# 7SegClock.net
KiCad netlist of a schematic drawn in EAGLE
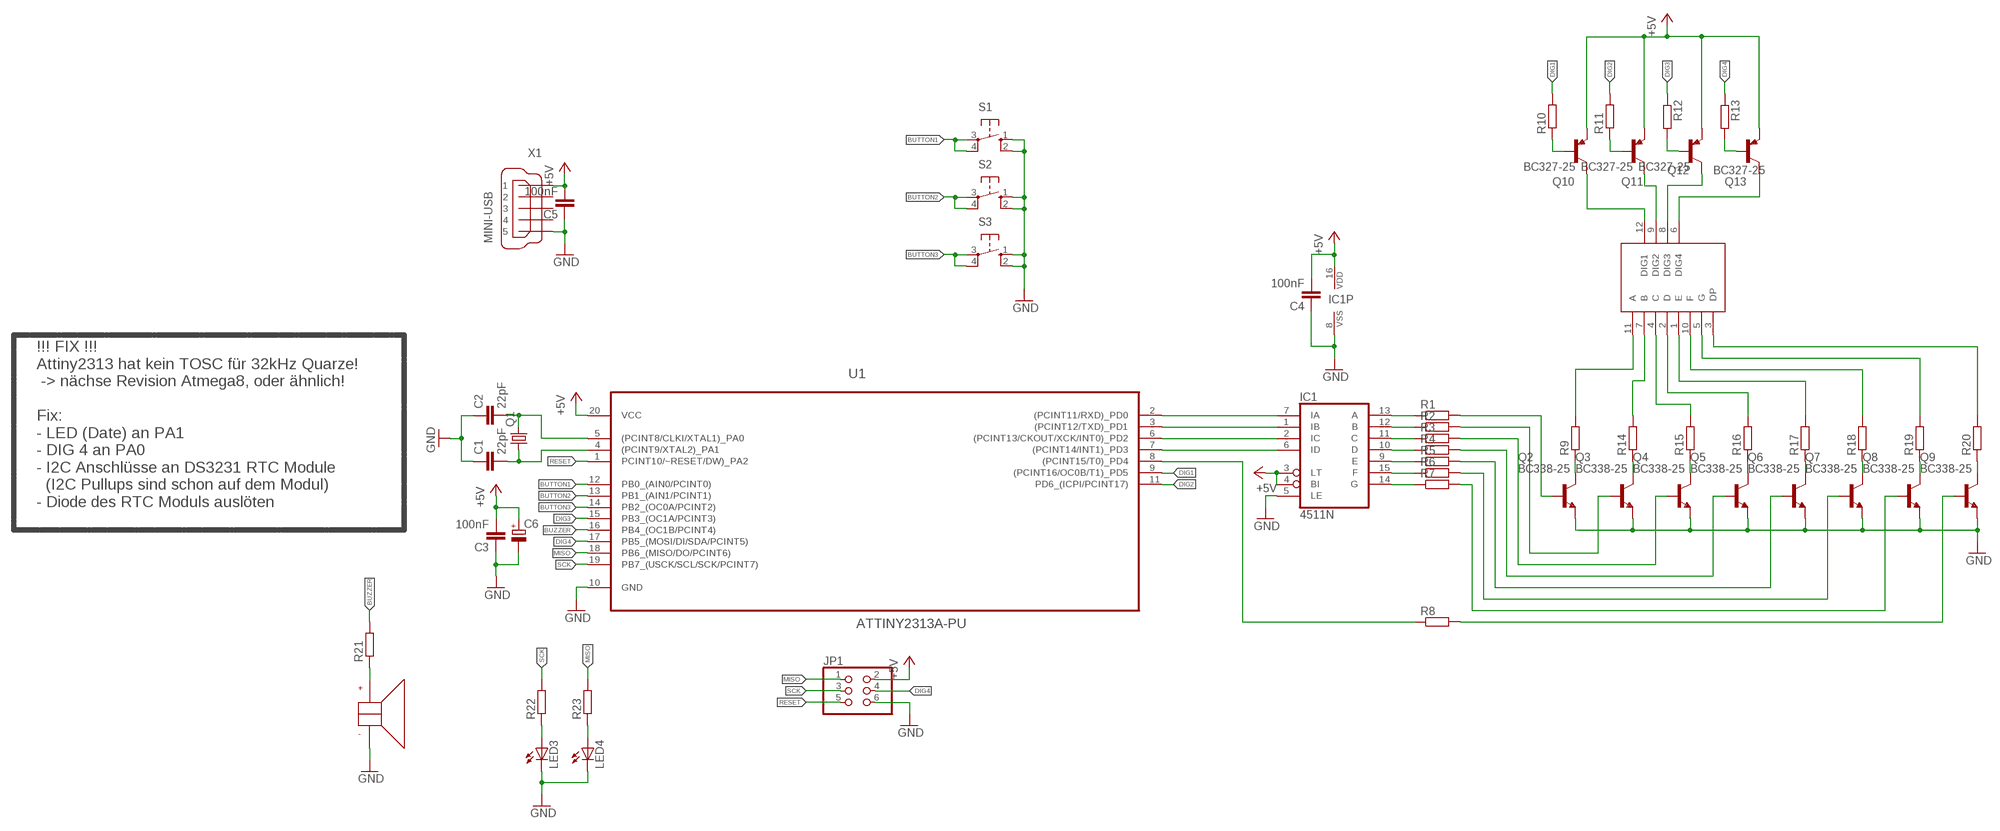
[diagram p0: schematic, sheet 1]

(export (version "E")
  (design (tool "Eeschema 10.0.6"))
  (components
    (comp (ref "C1")
      (value "22pF")
      (footprint "eagle-import:C025-025X050")
      (libsource (lib "eagle-import") (part "C-EU025-025X050"))
    )
    (comp (ref "C2")
      (value "22pF")
      (footprint "eagle-import:C025-025X050")
      (libsource (lib "eagle-import") (part "C-EU025-025X050"))
    )
    (comp (ref "C3")
      (value "100nF")
      (footprint "eagle-import:C025-025X050")
      (libsource (lib "eagle-import") (part "C-EU025-025X050"))
    )
    (comp (ref "C4")
      (value "100nF")
      (footprint "eagle-import:C025-025X050")
      (libsource (lib "eagle-import") (part "C-EU025-025X050"))
    )
    (comp (ref "C5")
      (value "100nF")
      (footprint "eagle-import:C025-025X050")
      (libsource (lib "eagle-import") (part "C-EU025-025X050"))
    )
    (comp (ref "C6")
      (value "CPOL-EUE2-5")
      (footprint "eagle-import:E2-5")
      (libsource (lib "eagle-import") (part "CPOL-EUE2-5"))
    )
    (comp (ref "IC1")
      (value "4511N")
      (footprint "eagle-import:DIL16")
      (libsource (lib "eagle-import") (part "4511N"))
    )
    (comp (ref "JP1")
      (value "PINHD-2X3")
      (footprint "eagle-import:2X03")
      (libsource (lib "eagle-import") (part "PINHD-2X3"))
    )
    (comp (ref "LED1")
      (value "7SEGCOMAN")
      (footprint "eagle-import:7SEGCOMAN")
      (libsource (lib "eagle-import") (part "7SEGCOMAN"))
    )
    (comp (ref "LED3")
      (value "LED3MM")
      (footprint "eagle-import:LED3MM")
      (libsource (lib "eagle-import") (part "LED3MM"))
    )
    (comp (ref "LED4")
      (value "LED3MM")
      (footprint "eagle-import:LED3MM")
      (libsource (lib "eagle-import") (part "LED3MM"))
    )
    (comp (ref "Q1")
      (value "CRYSTALTC38H")
      (footprint "eagle-import:TC38H")
      (libsource (lib "eagle-import") (part "CRYSTALTC38H"))
    )
    (comp (ref "Q2")
      (value "BC338-25")
      (footprint "eagle-import:TO92-EBC")
      (libsource (lib "eagle-import") (part "BC338-25"))
    )
    (comp (ref "Q3")
      (value "BC338-25")
      (footprint "eagle-import:TO92-EBC")
      (libsource (lib "eagle-import") (part "BC338-25"))
    )
    (comp (ref "Q4")
      (value "BC338-25")
      (footprint "eagle-import:TO92-EBC")
      (libsource (lib "eagle-import") (part "BC338-25"))
    )
    (comp (ref "Q5")
      (value "BC338-25")
      (footprint "eagle-import:TO92-EBC")
      (libsource (lib "eagle-import") (part "BC338-25"))
    )
    (comp (ref "Q6")
      (value "BC338-25")
      (footprint "eagle-import:TO92-EBC")
      (libsource (lib "eagle-import") (part "BC338-25"))
    )
    (comp (ref "Q7")
      (value "BC338-25")
      (footprint "eagle-import:TO92-EBC")
      (libsource (lib "eagle-import") (part "BC338-25"))
    )
    (comp (ref "Q8")
      (value "BC338-25")
      (footprint "eagle-import:TO92-EBC")
      (libsource (lib "eagle-import") (part "BC338-25"))
    )
    (comp (ref "Q9")
      (value "BC338-25")
      (footprint "eagle-import:TO92-EBC")
      (libsource (lib "eagle-import") (part "BC338-25"))
    )
    (comp (ref "Q10")
      (value "BC327-25")
      (footprint "eagle-import:TO92-EBC")
      (libsource (lib "eagle-import") (part "BC327-25"))
    )
    (comp (ref "Q11")
      (value "BC327-25")
      (footprint "eagle-import:TO92-EBC")
      (libsource (lib "eagle-import") (part "BC327-25"))
    )
    (comp (ref "Q12")
      (value "BC327-25")
      (footprint "eagle-import:TO92-EBC")
      (libsource (lib "eagle-import") (part "BC327-25"))
    )
    (comp (ref "Q13")
      (value "BC327-25")
      (footprint "eagle-import:TO92-EBC")
      (libsource (lib "eagle-import") (part "BC327-25"))
    )
    (comp (ref "R1")
      (value "R-EU_0207/7")
      (footprint "eagle-import:0207_7")
      (libsource (lib "eagle-import") (part "R-EU_0207/7"))
    )
    (comp (ref "R2")
      (value "R-EU_0207/7")
      (footprint "eagle-import:0207_7")
      (libsource (lib "eagle-import") (part "R-EU_0207/7"))
    )
    (comp (ref "R3")
      (value "R-EU_0207/7")
      (footprint "eagle-import:0207_7")
      (libsource (lib "eagle-import") (part "R-EU_0207/7"))
    )
    (comp (ref "R4")
      (value "R-EU_0207/7")
      (footprint "eagle-import:0207_7")
      (libsource (lib "eagle-import") (part "R-EU_0207/7"))
    )
    (comp (ref "R5")
      (value "R-EU_0207/7")
      (footprint "eagle-import:0207_7")
      (libsource (lib "eagle-import") (part "R-EU_0207/7"))
    )
    (comp (ref "R6")
      (value "R-EU_0207/7")
      (footprint "eagle-import:0207_7")
      (libsource (lib "eagle-import") (part "R-EU_0207/7"))
    )
    (comp (ref "R7")
      (value "R-EU_0207/7")
      (footprint "eagle-import:0207_7")
      (libsource (lib "eagle-import") (part "R-EU_0207/7"))
    )
    (comp (ref "R8")
      (value "R-EU_0207/7")
      (footprint "eagle-import:0207_7")
      (libsource (lib "eagle-import") (part "R-EU_0207/7"))
    )
    (comp (ref "R9")
      (value "R-EU_0207/7")
      (footprint "eagle-import:0207_7")
      (libsource (lib "eagle-import") (part "R-EU_0207/7"))
    )
    (comp (ref "R10")
      (value "R-EU_0207/7")
      (footprint "eagle-import:0207_7")
      (libsource (lib "eagle-import") (part "R-EU_0207/7"))
    )
    (comp (ref "R11")
      (value "R-EU_0207/7")
      (footprint "eagle-import:0207_7")
      (libsource (lib "eagle-import") (part "R-EU_0207/7"))
    )
    (comp (ref "R12")
      (value "R-EU_0207/7")
      (footprint "eagle-import:0207_7")
      (libsource (lib "eagle-import") (part "R-EU_0207/7"))
    )
    (comp (ref "R13")
      (value "R-EU_0207/7")
      (footprint "eagle-import:0207_7")
      (libsource (lib "eagle-import") (part "R-EU_0207/7"))
    )
    (comp (ref "R14")
      (value "R-EU_0207/7")
      (footprint "eagle-import:0207_7")
      (libsource (lib "eagle-import") (part "R-EU_0207/7"))
    )
    (comp (ref "R15")
      (value "R-EU_0207/7")
      (footprint "eagle-import:0207_7")
      (libsource (lib "eagle-import") (part "R-EU_0207/7"))
    )
    (comp (ref "R16")
      (value "R-EU_0207/7")
      (footprint "eagle-import:0207_7")
      (libsource (lib "eagle-import") (part "R-EU_0207/7"))
    )
    (comp (ref "R17")
      (value "R-EU_0207/7")
      (footprint "eagle-import:0207_7")
      (libsource (lib "eagle-import") (part "R-EU_0207/7"))
    )
    (comp (ref "R18")
      (value "R-EU_0207/7")
      (footprint "eagle-import:0207_7")
      (libsource (lib "eagle-import") (part "R-EU_0207/7"))
    )
    (comp (ref "R19")
      (value "R-EU_0207/7")
      (footprint "eagle-import:0207_7")
      (libsource (lib "eagle-import") (part "R-EU_0207/7"))
    )
    (comp (ref "R20")
      (value "R-EU_0207/7")
      (footprint "eagle-import:0207_7")
      (libsource (lib "eagle-import") (part "R-EU_0207/7"))
    )
    (comp (ref "R21")
      (value "R-EU_0207/7")
      (footprint "eagle-import:0207_7")
      (libsource (lib "eagle-import") (part "R-EU_0207/7"))
    )
    (comp (ref "R22")
      (value "R-EU_0207/7")
      (footprint "eagle-import:0207_7")
      (libsource (lib "eagle-import") (part "R-EU_0207/7"))
    )
    (comp (ref "R23")
      (value "R-EU_0207/7")
      (footprint "eagle-import:0207_7")
      (libsource (lib "eagle-import") (part "R-EU_0207/7"))
    )
    (comp (ref "S1")
      (value "10-XX")
      (footprint "eagle-import:B3F-10XX")
      (fields (field (name "MPN") "B3F-1000"))
      (libsource (lib "eagle-import") (part "10-XX"))
    )
    (comp (ref "S2")
      (value "10-XX")
      (footprint "eagle-import:B3F-10XX")
      (fields (field (name "MPN") "B3F-1000"))
      (libsource (lib "eagle-import") (part "10-XX"))
    )
    (comp (ref "S3")
      (value "10-XX")
      (footprint "eagle-import:B3F-10XX")
      (fields (field (name "MPN") "B3F-1000"))
      (libsource (lib "eagle-import") (part "10-XX"))
    )
    (comp (ref "U$1")
      (value "PIEZO_BUZZER_RM7,6")
      (footprint "eagle-import:PIEZO_BUZZER_RM7,6")
      (libsource (lib "eagle-import") (part "PIEZO_BUZZER_RM7,6"))
    )
    (comp (ref "U1")
      (value "ATTINY2313A-PU")
      (footprint "eagle-import:DIP254P762X533-20")
      (libsource (lib "eagle-import") (part "ATTINY2313A-PU"))
    )
    (comp (ref "X1")
      (value "MINI-USB")
      (footprint "eagle-import:32005-201")
      (libsource (lib "eagle-import") (part "MINI-USB-32005-201"))
    )
  )
  (nets
    (net (code "1") (name "+5V") (class "Default")
      (node (ref "C3") (pin "2") (pinfunction "2_2") (pintype "passive"))
      (node (ref "C4") (pin "2") (pinfunction "2_2") (pintype "passive"))
      (node (ref "C5") (pin "2") (pinfunction "2_2") (pintype "passive"))
      (node (ref "C6") (pin "+") (pinfunction "+_+") (pintype "passive"))
      (node (ref "IC1") (pin "16") (pinfunction "VDD_16") (pintype "power_in"))
      (node (ref "IC1") (pin "3") (pinfunction "LT_3") (pintype "input"))
      (node (ref "IC1") (pin "4") (pinfunction "BI_4") (pintype "input"))
      (node (ref "JP1") (pin "2") (pinfunction "2_2") (pintype "passive"))
      (node (ref "Q10") (pin "E") (pinfunction "E_E") (pintype "passive"))
      (node (ref "Q11") (pin "E") (pinfunction "E_E") (pintype "passive"))
      (node (ref "Q12") (pin "E") (pinfunction "E_E") (pintype "passive"))
      (node (ref "Q13") (pin "E") (pinfunction "E_E") (pintype "passive"))
      (node (ref "U1") (pin "20") (pinfunction "VCC_20") (pintype "power_in"))
      (node (ref "X1") (pin "1") (pinfunction "1_1") (pintype "passive"))
    )
    (net (code "2") (name "BUTTON1") (class "Default")
      (node (ref "S1") (pin "3") (pinfunction "P_3") (pintype "passive"))
      (node (ref "S1") (pin "4") (pinfunction "P1_4") (pintype "passive"))
      (node (ref "U1") (pin "12") (pinfunction "PB0_(AIN0/PCINT0)_12") (pintype "bidirectional"))
    )
    (net (code "3") (name "BUTTON2") (class "Default")
      (node (ref "S2") (pin "3") (pinfunction "P_3") (pintype "passive"))
      (node (ref "S2") (pin "4") (pinfunction "P1_4") (pintype "passive"))
      (node (ref "U1") (pin "13") (pinfunction "PB1_(AIN1/PCINT1)_13") (pintype "bidirectional"))
    )
    (net (code "4") (name "BUTTON3") (class "Default")
      (node (ref "S3") (pin "3") (pinfunction "P_3") (pintype "passive"))
      (node (ref "S3") (pin "4") (pinfunction "P1_4") (pintype "passive"))
      (node (ref "U1") (pin "14") (pinfunction "PB2_(OC0A/PCINT2)_14") (pintype "bidirectional"))
    )
    (net (code "5") (name "BUZZER") (class "Default")
      (node (ref "R21") (pin "2") (pinfunction "2_2") (pintype "passive"))
      (node (ref "U1") (pin "16") (pinfunction "PB4_(OC1B/PCINT4)_16") (pintype "bidirectional"))
    )
    (net (code "6") (name "DIG1") (class "Default")
      (node (ref "R10") (pin "2") (pinfunction "2_2") (pintype "passive"))
      (node (ref "U1") (pin "9") (pinfunction "(PCINT16/OC0B/T1)_PD5_9") (pintype "bidirectional"))
    )
    (net (code "7") (name "DIG2") (class "Default")
      (node (ref "R11") (pin "2") (pinfunction "2_2") (pintype "passive"))
      (node (ref "U1") (pin "11") (pinfunction "PD6_(ICPI/PCINT17)_11") (pintype "bidirectional"))
    )
    (net (code "8") (name "DIG3") (class "Default")
      (node (ref "R12") (pin "1") (pinfunction "1_1") (pintype "passive"))
      (node (ref "U1") (pin "15") (pinfunction "PB3_(OC1A/PCINT3)_15") (pintype "bidirectional"))
    )
    (net (code "9") (name "DIG4") (class "Default")
      (node (ref "JP1") (pin "4") (pinfunction "4_4") (pintype "passive"))
      (node (ref "R13") (pin "1") (pinfunction "1_1") (pintype "passive"))
      (node (ref "U1") (pin "17") (pinfunction "PB5_(MOSI/DI/SDA/PCINT5)_17") (pintype "bidirectional"))
    )
    (net (code "10") (name "GND") (class "Default")
      (node (ref "C1") (pin "1") (pinfunction "1_1") (pintype "passive"))
      (node (ref "C2") (pin "1") (pinfunction "1_1") (pintype "passive"))
      (node (ref "C3") (pin "1") (pinfunction "1_1") (pintype "passive"))
      (node (ref "C4") (pin "1") (pinfunction "1_1") (pintype "passive"))
      (node (ref "C5") (pin "1") (pinfunction "1_1") (pintype "passive"))
      (node (ref "C6") (pin "-") (pinfunction "-_-") (pintype "passive"))
      (node (ref "IC1") (pin "5") (pinfunction "LE_5") (pintype "input"))
      (node (ref "IC1") (pin "8") (pinfunction "VSS_8") (pintype "power_in"))
      (node (ref "JP1") (pin "6") (pinfunction "6_6") (pintype "passive"))
      (node (ref "LED3") (pin "K") (pinfunction "C_K") (pintype "passive"))
      (node (ref "LED4") (pin "K") (pinfunction "C_K") (pintype "passive"))
      (node (ref "Q2") (pin "E") (pinfunction "E_E") (pintype "passive"))
      (node (ref "Q3") (pin "E") (pinfunction "E_E") (pintype "passive"))
      (node (ref "Q4") (pin "E") (pinfunction "E_E") (pintype "passive"))
      (node (ref "Q5") (pin "E") (pinfunction "E_E") (pintype "passive"))
      (node (ref "Q6") (pin "E") (pinfunction "E_E") (pintype "passive"))
      (node (ref "Q7") (pin "E") (pinfunction "E_E") (pintype "passive"))
      (node (ref "Q8") (pin "E") (pinfunction "E_E") (pintype "passive"))
      (node (ref "Q9") (pin "E") (pinfunction "E_E") (pintype "passive"))
      (node (ref "S1") (pin "1") (pinfunction "S_1") (pintype "passive"))
      (node (ref "S1") (pin "2") (pinfunction "S1_2") (pintype "passive"))
      (node (ref "S2") (pin "1") (pinfunction "S_1") (pintype "passive"))
      (node (ref "S2") (pin "2") (pinfunction "S1_2") (pintype "passive"))
      (node (ref "S3") (pin "1") (pinfunction "S_1") (pintype "passive"))
      (node (ref "S3") (pin "2") (pinfunction "S1_2") (pintype "passive"))
      (node (ref "U$1") (pin "P$2") (pinfunction "P$2_P$2") (pintype "bidirectional"))
      (node (ref "U1") (pin "10") (pinfunction "GND_10") (pintype "passive"))
      (node (ref "X1") (pin "5") (pinfunction "5_5") (pintype "passive"))
    )
    (net (code "11") (name "MISO") (class "Default")
      (node (ref "JP1") (pin "1") (pinfunction "1_1") (pintype "passive"))
      (node (ref "R23") (pin "2") (pinfunction "2_2") (pintype "passive"))
      (node (ref "U1") (pin "18") (pinfunction "PB6_(MISO/DO/PCINT6)_18") (pintype "bidirectional"))
    )
    (net (code "12") (name "Net-(IC1A-A)") (class "Default")
      (node (ref "IC1") (pin "13") (pinfunction "A_13") (pintype "output"))
      (node (ref "R1") (pin "1") (pinfunction "1_1") (pintype "passive"))
    )
    (net (code "13") (name "Net-(IC1A-B)") (class "Default")
      (node (ref "IC1") (pin "12") (pinfunction "B_12") (pintype "output"))
      (node (ref "R2") (pin "1") (pinfunction "1_1") (pintype "passive"))
    )
    (net (code "14") (name "Net-(IC1A-C)") (class "Default")
      (node (ref "IC1") (pin "11") (pinfunction "C_11") (pintype "output"))
      (node (ref "R3") (pin "1") (pinfunction "1_1") (pintype "passive"))
    )
    (net (code "15") (name "Net-(IC1A-D)") (class "Default")
      (node (ref "IC1") (pin "10") (pinfunction "D_10") (pintype "output"))
      (node (ref "R4") (pin "1") (pinfunction "1_1") (pintype "passive"))
    )
    (net (code "16") (name "Net-(IC1A-E)") (class "Default")
      (node (ref "IC1") (pin "9") (pinfunction "E_9") (pintype "output"))
      (node (ref "R5") (pin "1") (pinfunction "1_1") (pintype "passive"))
    )
    (net (code "17") (name "Net-(IC1A-F)") (class "Default")
      (node (ref "IC1") (pin "15") (pinfunction "F_15") (pintype "output"))
      (node (ref "R6") (pin "1") (pinfunction "1_1") (pintype "passive"))
    )
    (net (code "18") (name "Net-(IC1A-G)") (class "Default")
      (node (ref "IC1") (pin "14") (pinfunction "G_14") (pintype "output"))
      (node (ref "R7") (pin "1") (pinfunction "1_1") (pintype "passive"))
    )
    (net (code "19") (name "Net-(IC1A-IA)") (class "Default")
      (node (ref "IC1") (pin "7") (pinfunction "IA_7") (pintype "input"))
      (node (ref "U1") (pin "2") (pinfunction "(PCINT11/RXD)_PD0_2") (pintype "bidirectional"))
    )
    (net (code "20") (name "Net-(IC1A-IB)") (class "Default")
      (node (ref "IC1") (pin "1") (pinfunction "IB_1") (pintype "input"))
      (node (ref "U1") (pin "3") (pinfunction "(PCINT12/TXD)_PD1_3") (pintype "bidirectional"))
    )
    (net (code "21") (name "Net-(IC1A-IC)") (class "Default")
      (node (ref "IC1") (pin "2") (pinfunction "IC_2") (pintype "input"))
      (node (ref "U1") (pin "6") (pinfunction "(PCINT13/CKOUT/XCK/INT0)_PD2_6") (pintype "bidirectional"))
    )
    (net (code "22") (name "Net-(IC1A-ID)") (class "Default")
      (node (ref "IC1") (pin "6") (pinfunction "ID_6") (pintype "input"))
      (node (ref "U1") (pin "7") (pinfunction "(PCINT14/INT1)_PD3_7") (pintype "bidirectional"))
    )
    (net (code "23") (name "Net-(LED1-A)") (class "Default")
      (node (ref "LED1") (pin "11") (pinfunction "A_11") (pintype "bidirectional"))
      (node (ref "R9") (pin "2") (pinfunction "2_2") (pintype "passive"))
    )
    (net (code "24") (name "Net-(LED1-B)") (class "Default")
      (node (ref "LED1") (pin "7") (pinfunction "B_7") (pintype "bidirectional"))
      (node (ref "R14") (pin "2") (pinfunction "2_2") (pintype "passive"))
    )
    (net (code "25") (name "Net-(LED1-C)") (class "Default")
      (node (ref "LED1") (pin "4") (pinfunction "C_4") (pintype "bidirectional"))
      (node (ref "R15") (pin "2") (pinfunction "2_2") (pintype "passive"))
    )
    (net (code "26") (name "Net-(LED1-D)") (class "Default")
      (node (ref "LED1") (pin "2") (pinfunction "D_2") (pintype "bidirectional"))
      (node (ref "R16") (pin "2") (pinfunction "2_2") (pintype "passive"))
    )
    (net (code "27") (name "Net-(LED1-DIG1)") (class "Default")
      (node (ref "LED1") (pin "12") (pinfunction "DIG1_12") (pintype "bidirectional"))
      (node (ref "Q10") (pin "C") (pinfunction "C_C") (pintype "passive"))
    )
    (net (code "28") (name "Net-(LED1-DIG2)") (class "Default")
      (node (ref "LED1") (pin "9") (pinfunction "DIG2_9") (pintype "bidirectional"))
      (node (ref "Q11") (pin "C") (pinfunction "C_C") (pintype "passive"))
    )
    (net (code "29") (name "Net-(LED1-DIG3)") (class "Default")
      (node (ref "LED1") (pin "8") (pinfunction "DIG3_8") (pintype "bidirectional"))
      (node (ref "Q12") (pin "C") (pinfunction "C_C") (pintype "passive"))
    )
    (net (code "30") (name "Net-(LED1-DIG4)") (class "Default")
      (node (ref "LED1") (pin "6") (pinfunction "DIG4_6") (pintype "bidirectional"))
      (node (ref "Q13") (pin "C") (pinfunction "C_C") (pintype "passive"))
    )
    (net (code "31") (name "Net-(LED1-DP)") (class "Default")
      (node (ref "LED1") (pin "3") (pinfunction "DP_3") (pintype "bidirectional"))
      (node (ref "R20") (pin "2") (pinfunction "2_2") (pintype "passive"))
    )
    (net (code "32") (name "Net-(LED1-E)") (class "Default")
      (node (ref "LED1") (pin "1") (pinfunction "E_1") (pintype "bidirectional"))
      (node (ref "R17") (pin "2") (pinfunction "2_2") (pintype "passive"))
    )
    (net (code "33") (name "Net-(LED1-F)") (class "Default")
      (node (ref "LED1") (pin "10") (pinfunction "F_10") (pintype "bidirectional"))
      (node (ref "R18") (pin "2") (pinfunction "2_2") (pintype "passive"))
    )
    (net (code "34") (name "Net-(LED1-G)") (class "Default")
      (node (ref "LED1") (pin "5") (pinfunction "G_5") (pintype "bidirectional"))
      (node (ref "R19") (pin "2") (pinfunction "2_2") (pintype "passive"))
    )
    (net (code "35") (name "Net-(LED3-PadA)") (class "Default")
      (node (ref "LED3") (pin "A") (pinfunction "A_A") (pintype "passive"))
      (node (ref "R22") (pin "1") (pinfunction "1_1") (pintype "passive"))
    )
    (net (code "36") (name "Net-(LED4-PadA)") (class "Default")
      (node (ref "LED4") (pin "A") (pinfunction "A_A") (pintype "passive"))
      (node (ref "R23") (pin "1") (pinfunction "1_1") (pintype "passive"))
    )
    (net (code "37") (name "Net-(Q2-PadB)") (class "Default")
      (node (ref "Q2") (pin "B") (pinfunction "B_B") (pintype "passive"))
      (node (ref "R1") (pin "2") (pinfunction "2_2") (pintype "passive"))
    )
    (net (code "38") (name "Net-(Q2-PadC)") (class "Default")
      (node (ref "Q2") (pin "C") (pinfunction "C_C") (pintype "passive"))
      (node (ref "R9") (pin "1") (pinfunction "1_1") (pintype "passive"))
    )
    (net (code "39") (name "Net-(Q3-PadB)") (class "Default")
      (node (ref "Q3") (pin "B") (pinfunction "B_B") (pintype "passive"))
      (node (ref "R2") (pin "2") (pinfunction "2_2") (pintype "passive"))
    )
    (net (code "40") (name "Net-(Q3-PadC)") (class "Default")
      (node (ref "Q3") (pin "C") (pinfunction "C_C") (pintype "passive"))
      (node (ref "R14") (pin "1") (pinfunction "1_1") (pintype "passive"))
    )
    (net (code "41") (name "Net-(Q4-PadB)") (class "Default")
      (node (ref "Q4") (pin "B") (pinfunction "B_B") (pintype "passive"))
      (node (ref "R3") (pin "2") (pinfunction "2_2") (pintype "passive"))
    )
    (net (code "42") (name "Net-(Q4-PadC)") (class "Default")
      (node (ref "Q4") (pin "C") (pinfunction "C_C") (pintype "passive"))
      (node (ref "R15") (pin "1") (pinfunction "1_1") (pintype "passive"))
    )
    (net (code "43") (name "Net-(Q5-PadB)") (class "Default")
      (node (ref "Q5") (pin "B") (pinfunction "B_B") (pintype "passive"))
      (node (ref "R4") (pin "2") (pinfunction "2_2") (pintype "passive"))
    )
    (net (code "44") (name "Net-(Q5-PadC)") (class "Default")
      (node (ref "Q5") (pin "C") (pinfunction "C_C") (pintype "passive"))
      (node (ref "R16") (pin "1") (pinfunction "1_1") (pintype "passive"))
    )
    (net (code "45") (name "Net-(Q6-PadB)") (class "Default")
      (node (ref "Q6") (pin "B") (pinfunction "B_B") (pintype "passive"))
      (node (ref "R5") (pin "2") (pinfunction "2_2") (pintype "passive"))
    )
    (net (code "46") (name "Net-(Q6-PadC)") (class "Default")
      (node (ref "Q6") (pin "C") (pinfunction "C_C") (pintype "passive"))
      (node (ref "R17") (pin "1") (pinfunction "1_1") (pintype "passive"))
    )
    (net (code "47") (name "Net-(Q7-PadB)") (class "Default")
      (node (ref "Q7") (pin "B") (pinfunction "B_B") (pintype "passive"))
      (node (ref "R6") (pin "2") (pinfunction "2_2") (pintype "passive"))
    )
    (net (code "48") (name "Net-(Q7-PadC)") (class "Default")
      (node (ref "Q7") (pin "C") (pinfunction "C_C") (pintype "passive"))
      (node (ref "R18") (pin "1") (pinfunction "1_1") (pintype "passive"))
    )
    (net (code "49") (name "Net-(Q8-PadB)") (class "Default")
      (node (ref "Q8") (pin "B") (pinfunction "B_B") (pintype "passive"))
      (node (ref "R7") (pin "2") (pinfunction "2_2") (pintype "passive"))
    )
    (net (code "50") (name "Net-(Q8-PadC)") (class "Default")
      (node (ref "Q8") (pin "C") (pinfunction "C_C") (pintype "passive"))
      (node (ref "R19") (pin "1") (pinfunction "1_1") (pintype "passive"))
    )
    (net (code "51") (name "Net-(Q9-PadB)") (class "Default")
      (node (ref "Q9") (pin "B") (pinfunction "B_B") (pintype "passive"))
      (node (ref "R8") (pin "2") (pinfunction "2_2") (pintype "passive"))
    )
    (net (code "52") (name "Net-(Q9-PadC)") (class "Default")
      (node (ref "Q9") (pin "C") (pinfunction "C_C") (pintype "passive"))
      (node (ref "R20") (pin "1") (pinfunction "1_1") (pintype "passive"))
    )
    (net (code "53") (name "Net-(Q10-PadB)") (class "Default")
      (node (ref "Q10") (pin "B") (pinfunction "B_B") (pintype "passive"))
      (node (ref "R10") (pin "1") (pinfunction "1_1") (pintype "passive"))
    )
    (net (code "54") (name "Net-(Q11-PadB)") (class "Default")
      (node (ref "Q11") (pin "B") (pinfunction "B_B") (pintype "passive"))
      (node (ref "R11") (pin "1") (pinfunction "1_1") (pintype "passive"))
    )
    (net (code "55") (name "Net-(Q12-PadB)") (class "Default")
      (node (ref "Q12") (pin "B") (pinfunction "B_B") (pintype "passive"))
      (node (ref "R12") (pin "2") (pinfunction "2_2") (pintype "passive"))
    )
    (net (code "56") (name "Net-(Q13-PadB)") (class "Default")
      (node (ref "Q13") (pin "B") (pinfunction "B_B") (pintype "passive"))
      (node (ref "R13") (pin "2") (pinfunction "2_2") (pintype "passive"))
    )
    (net (code "57") (name "Net-(R21-Pad1)") (class "Default")
      (node (ref "R21") (pin "1") (pinfunction "1_1") (pintype "passive"))
      (node (ref "U$1") (pin "P$1") (pinfunction "P$1_P$1") (pintype "bidirectional"))
    )
    (net (code "58") (name "Net-(U1-(PCINT8{slash}CLKI{slash}XTAL1)_PA0)") (class "Default")
      (node (ref "C2") (pin "2") (pinfunction "2_2") (pintype "passive"))
      (node (ref "Q1") (pin "2") (pinfunction "2_2") (pintype "passive"))
      (node (ref "U1") (pin "5") (pinfunction "(PCINT8/CLKI/XTAL1)_PA0_5") (pintype "bidirectional"))
    )
    (net (code "59") (name "Net-(U1-(PCINT9{slash}XTAL2)_PA1)") (class "Default")
      (node (ref "C1") (pin "2") (pinfunction "2_2") (pintype "passive"))
      (node (ref "Q1") (pin "1") (pinfunction "1_1") (pintype "passive"))
      (node (ref "U1") (pin "4") (pinfunction "(PCINT9/XTAL2)_PA1_4") (pintype "bidirectional"))
    )
    (net (code "60") (name "Net-(U1-(PCINT15{slash}T0)_PD4)") (class "Default")
      (node (ref "R8") (pin "1") (pinfunction "1_1") (pintype "passive"))
      (node (ref "U1") (pin "8") (pinfunction "(PCINT15/T0)_PD4_8") (pintype "bidirectional"))
    )
    (net (code "61") (name "RESET") (class "Default")
      (node (ref "JP1") (pin "5") (pinfunction "5_5") (pintype "passive"))
      (node (ref "U1") (pin "1") (pinfunction "PCINT10/~{RESET/DW})_PA2_1") (pintype "bidirectional"))
    )
    (net (code "62") (name "SCK") (class "Default")
      (node (ref "JP1") (pin "3") (pinfunction "3_3") (pintype "passive"))
      (node (ref "R22") (pin "2") (pinfunction "2_2") (pintype "passive"))
      (node (ref "U1") (pin "19") (pinfunction "PB7_(USCK/SCL/SCK/PCINT7)_19") (pintype "bidirectional"))
    )
    (net (code "63") (name "unconnected-(X1-Pad2)") (class "Default")
      (node (ref "X1") (pin "2") (pinfunction "2_2") (pintype "passive"))
    )
    (net (code "64") (name "unconnected-(X1-Pad3)") (class "Default")
      (node (ref "X1") (pin "3") (pinfunction "3_3") (pintype "passive"))
    )
    (net (code "65") (name "unconnected-(X1-Pad4)") (class "Default")
      (node (ref "X1") (pin "4") (pinfunction "4_4") (pintype "passive"))
    )
  )
)
